# ESP8266.net
KiCad netlist of a schematic drawn in EAGLE
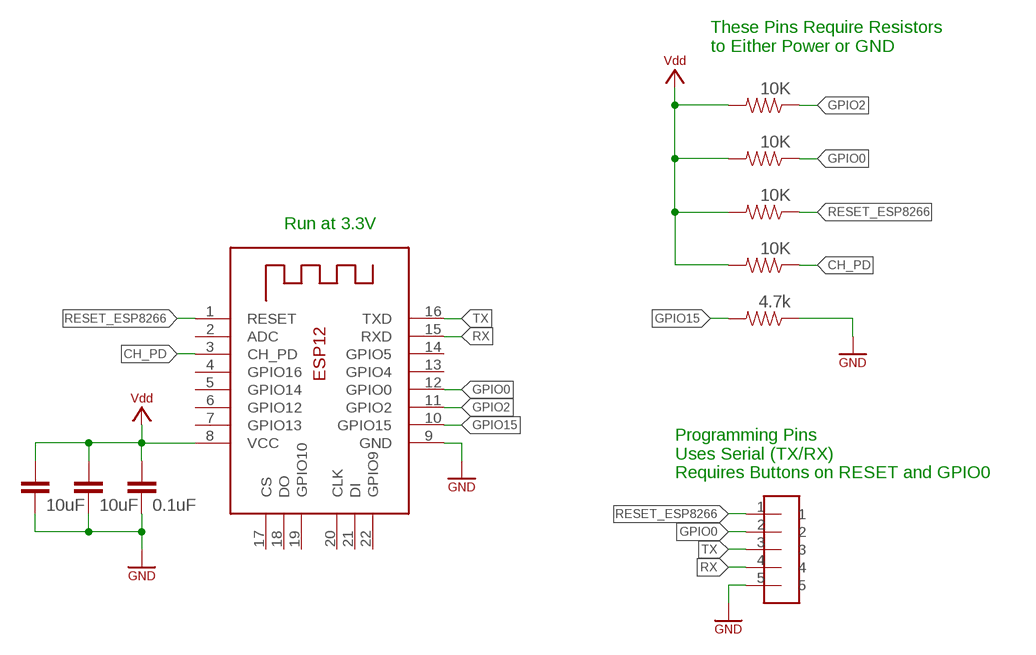
[diagram p0: schematic, sheet 1]

(export (version "E")
  (design (tool "Eeschema 10.0.6"))
  (components
    (comp (ref "C1")
      (value "0.1uF")
      (footprint "eagle-import:0805")
      (libsource (lib "eagle-import") (part "COMPONENT_CAP-0805"))
    )
    (comp (ref "C2")
      (value "10uF")
      (footprint "eagle-import:0805")
      (libsource (lib "eagle-import") (part "COMPONENT_CAP-0805"))
    )
    (comp (ref "C3")
      (value "10uF")
      (footprint "eagle-import:0805")
      (libsource (lib "eagle-import") (part "COMPONENT_CAP-0805"))
    )
    (comp (ref "R1")
      (value "10K")
      (footprint "eagle-import:0805")
      (libsource (lib "eagle-import") (part "COMPONENT_RESISTOR-0805"))
    )
    (comp (ref "R2")
      (value "10K")
      (footprint "eagle-import:0805")
      (libsource (lib "eagle-import") (part "COMPONENT_RESISTOR-0805"))
    )
    (comp (ref "R3")
      (value "10K")
      (footprint "eagle-import:0805")
      (libsource (lib "eagle-import") (part "COMPONENT_RESISTOR-0805"))
    )
    (comp (ref "R4")
      (value "10K")
      (footprint "eagle-import:0805")
      (libsource (lib "eagle-import") (part "COMPONENT_RESISTOR-0805"))
    )
    (comp (ref "R5")
      (value "4.7k")
      (footprint "eagle-import:0805")
      (libsource (lib "eagle-import") (part "COMPONENT_RESISTOR-0805"))
    )
    (comp (ref "U$1")
      (value "HEADER-5-TESTPOINT")
      (footprint "eagle-import:TESTPOINT-5")
      (libsource (lib "eagle-import") (part "HEADER-5-TESTPOINT"))
    )
    (comp (ref "X1")
      (value "MICRO_ESP8266")
      (footprint "eagle-import:ESP-12E")
      (libsource (lib "eagle-import") (part "MICRO_ESP8266"))
    )
  )
  (nets
    (net (code "1") (name "CH_PD") (class "Default")
      (node (ref "R4") (pin "1") (pinfunction "1_1") (pintype "passive"))
      (node (ref "X1") (pin "3") (pinfunction "CH_PD_3") (pintype "input"))
    )
    (net (code "2") (name "GPIO0") (class "Default")
      (node (ref "R2") (pin "1") (pinfunction "1_1") (pintype "passive"))
      (node (ref "U$1") (pin "2") (pinfunction "2_2") (pintype "bidirectional"))
      (node (ref "X1") (pin "12") (pinfunction "GPIO0_12") (pintype "bidirectional"))
    )
    (net (code "3") (name "GPIO2") (class "Default")
      (node (ref "R1") (pin "1") (pinfunction "1_1") (pintype "passive"))
      (node (ref "X1") (pin "11") (pinfunction "GPIO2_11") (pintype "bidirectional"))
    )
    (net (code "4") (name "GPIO15") (class "Default")
      (node (ref "R5") (pin "2") (pinfunction "2_2") (pintype "passive"))
      (node (ref "X1") (pin "10") (pinfunction "GPIO15_10") (pintype "bidirectional"))
    )
    (net (code "5") (name "RESET_ESP8266") (class "Default")
      (node (ref "R3") (pin "1") (pinfunction "1_1") (pintype "passive"))
      (node (ref "U$1") (pin "1") (pinfunction "1_1") (pintype "bidirectional"))
      (node (ref "X1") (pin "1") (pinfunction "RESET_1") (pintype "input"))
    )
    (net (code "6") (name "RX") (class "Default")
      (node (ref "U$1") (pin "4") (pinfunction "4_4") (pintype "bidirectional"))
      (node (ref "X1") (pin "15") (pinfunction "RXD_15") (pintype "input"))
    )
    (net (code "7") (name "SYMBOL_GND") (class "Default")
      (node (ref "C1") (pin "2") (pinfunction "2_2") (pintype "passive"))
      (node (ref "C2") (pin "2") (pinfunction "2_2") (pintype "passive"))
      (node (ref "C3") (pin "2") (pinfunction "2_2") (pintype "passive"))
      (node (ref "R5") (pin "1") (pinfunction "1_1") (pintype "passive"))
      (node (ref "U$1") (pin "5") (pinfunction "5_5") (pintype "bidirectional"))
      (node (ref "X1") (pin "9") (pinfunction "GND_9") (pintype "power_in"))
    )
    (net (code "8") (name "SYMBOL_VDD") (class "Default")
      (node (ref "C1") (pin "1") (pinfunction "1_1") (pintype "passive"))
      (node (ref "C2") (pin "1") (pinfunction "1_1") (pintype "passive"))
      (node (ref "C3") (pin "1") (pinfunction "1_1") (pintype "passive"))
      (node (ref "R1") (pin "2") (pinfunction "2_2") (pintype "passive"))
      (node (ref "R2") (pin "2") (pinfunction "2_2") (pintype "passive"))
      (node (ref "R3") (pin "2") (pinfunction "2_2") (pintype "passive"))
      (node (ref "R4") (pin "2") (pinfunction "2_2") (pintype "passive"))
      (node (ref "X1") (pin "8") (pinfunction "VCC_8") (pintype "power_in"))
    )
    (net (code "9") (name "TX") (class "Default")
      (node (ref "U$1") (pin "3") (pinfunction "3_3") (pintype "bidirectional"))
      (node (ref "X1") (pin "16") (pinfunction "TXD_16") (pintype "output"))
    )
    (net (code "10") (name "unconnected-(X1-ADC-Pad2)") (class "Default")
      (node (ref "X1") (pin "2") (pinfunction "ADC_2") (pintype "passive"))
    )
    (net (code "11") (name "unconnected-(X1-CLK-Pad20)") (class "Default")
      (node (ref "X1") (pin "20") (pinfunction "CLK_20") (pintype "bidirectional"))
    )
    (net (code "12") (name "unconnected-(X1-CS-Pad17)") (class "Default")
      (node (ref "X1") (pin "17") (pinfunction "CS_17") (pintype "bidirectional"))
    )
    (net (code "13") (name "unconnected-(X1-DI-Pad21)") (class "Default")
      (node (ref "X1") (pin "21") (pinfunction "DI_21") (pintype "bidirectional"))
    )
    (net (code "14") (name "unconnected-(X1-DO-Pad18)") (class "Default")
      (node (ref "X1") (pin "18") (pinfunction "DO_18") (pintype "bidirectional"))
    )
    (net (code "15") (name "unconnected-(X1-GPIO4-Pad13)") (class "Default")
      (node (ref "X1") (pin "13") (pinfunction "GPIO4_13") (pintype "bidirectional"))
    )
    (net (code "16") (name "unconnected-(X1-GPIO5-Pad14)") (class "Default")
      (node (ref "X1") (pin "14") (pinfunction "GPIO5_14") (pintype "bidirectional"))
    )
    (net (code "17") (name "unconnected-(X1-GPIO9-Pad22)") (class "Default")
      (node (ref "X1") (pin "22") (pinfunction "GPIO9_22") (pintype "bidirectional"))
    )
    (net (code "18") (name "unconnected-(X1-GPIO10-Pad19)") (class "Default")
      (node (ref "X1") (pin "19") (pinfunction "GPIO10_19") (pintype "bidirectional"))
    )
    (net (code "19") (name "unconnected-(X1-GPIO12-Pad6)") (class "Default")
      (node (ref "X1") (pin "6") (pinfunction "GPIO12_6") (pintype "bidirectional"))
    )
    (net (code "20") (name "unconnected-(X1-GPIO13-Pad7)") (class "Default")
      (node (ref "X1") (pin "7") (pinfunction "GPIO13_7") (pintype "bidirectional"))
    )
    (net (code "21") (name "unconnected-(X1-GPIO14-Pad5)") (class "Default")
      (node (ref "X1") (pin "5") (pinfunction "GPIO14_5") (pintype "bidirectional"))
    )
    (net (code "22") (name "unconnected-(X1-GPIO16-Pad4)") (class "Default")
      (node (ref "X1") (pin "4") (pinfunction "GPIO16_4") (pintype "bidirectional"))
    )
  )
)
